# USB_Type_A_Female_Breakout.net
KiCad netlist of a schematic drawn in EAGLE
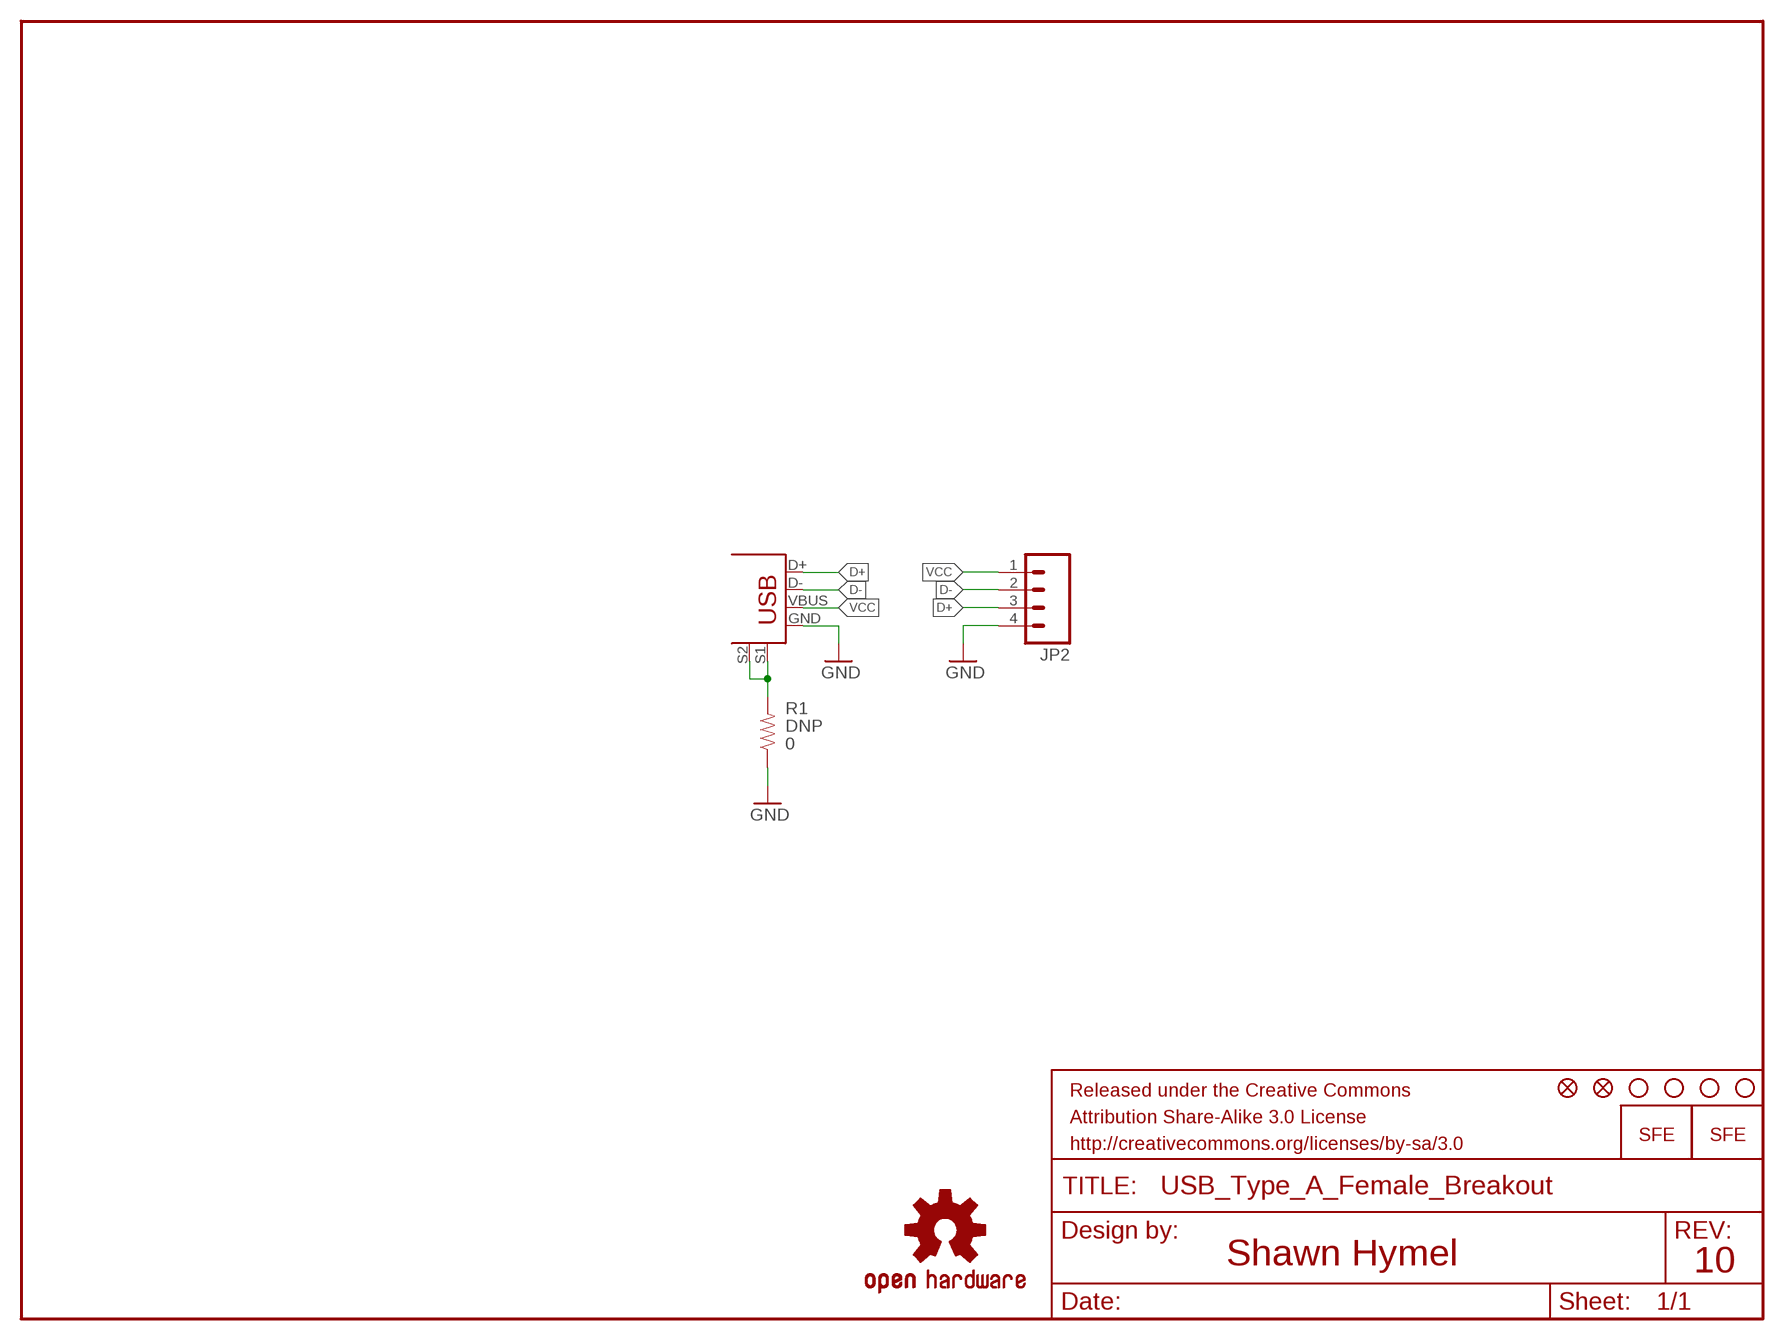
[diagram p0: schematic, sheet 1]

(export (version "E")
  (design (tool "Eeschema 10.0.6"))
  (components
    (comp (ref "FID1")
      (value "FIDUCIAL1X2")
      (footprint "eagle-import:FIDUCIAL-1X2")
      (libsource (lib "eagle-import") (part "FIDUCIAL1X2"))
    )
    (comp (ref "FID2")
      (value "FIDUCIAL1X2")
      (footprint "eagle-import:FIDUCIAL-1X2")
      (libsource (lib "eagle-import") (part "FIDUCIAL1X2"))
    )
    (comp (ref "FRAME1")
      (value "FRAME-LETTER")
      (footprint "eagle-import:CREATIVE_COMMONS")
      (libsource (lib "eagle-import") (part "FRAME-LETTER"))
    )
    (comp (ref "JP1")
      (value "USB+SHIELDUSB-A-S-NOSILK-FEMALE")
      (footprint "eagle-import:USB-A-S-NOSILK-FEMALE")
      (libsource (lib "eagle-import") (part "USB+SHIELDUSB-A-S-NOSILK-FEMALE"))
    )
    (comp (ref "JP2")
      (value "M04PTH")
      (footprint "eagle-import:1X04")
      (libsource (lib "eagle-import") (part "M04PTH"))
    )
    (comp (ref "LOGO1")
      (value "LOGO-SFENEW")
      (footprint "eagle-import:SFE-NEW-WEBLOGO")
      (libsource (lib "eagle-import") (part "LOGO-SFENEW"))
    )
    (comp (ref "LOGO2")
      (value "OSHW-LOGOS")
      (footprint "eagle-import:OSHW-LOGO-S")
      (libsource (lib "eagle-import") (part "OSHW-LOGOS"))
    )
    (comp (ref "LOGO3")
      (value "LOGO-SFESK")
      (footprint "eagle-import:SFE-LOGO-FLAME")
      (libsource (lib "eagle-import") (part "LOGO-SFESK"))
    )
    (comp (ref "R1")
      (value "0")
      (footprint "eagle-import:0603-RES")
      (fields (field (name "PLACE") "DNP"))
      (libsource (lib "eagle-import") (part "RESISTOR0603"))
    )
    (comp (ref "STANDOFF1")
      (value "STAND-OFF")
      (footprint "eagle-import:STAND-OFF")
      (libsource (lib "eagle-import") (part "STAND-OFF"))
    )
    (comp (ref "STANDOFF2")
      (value "STAND-OFF")
      (footprint "eagle-import:STAND-OFF")
      (libsource (lib "eagle-import") (part "STAND-OFF"))
    )
    (comp (ref "STANDOFF3")
      (value "STAND-OFF")
      (footprint "eagle-import:STAND-OFF")
      (libsource (lib "eagle-import") (part "STAND-OFF"))
    )
    (comp (ref "STANDOFF4")
      (value "STAND-OFF")
      (footprint "eagle-import:STAND-OFF")
      (libsource (lib "eagle-import") (part "STAND-OFF"))
    )
  )
  (nets
    (net (code "1") (name "D+") (class "Default")
      (node (ref "JP1") (pin "D+") (pinfunction "D+_D+") (pintype "bidirectional"))
      (node (ref "JP2") (pin "3") (pinfunction "3_3") (pintype "passive"))
    )
    (net (code "2") (name "D-") (class "Default")
      (node (ref "JP1") (pin "D-") (pinfunction "D-_D-") (pintype "bidirectional"))
      (node (ref "JP2") (pin "2") (pinfunction "2_2") (pintype "passive"))
    )
    (net (code "3") (name "GND") (class "Default")
      (node (ref "JP1") (pin "GND") (pinfunction "GND_GND") (pintype "bidirectional"))
      (node (ref "JP2") (pin "4") (pinfunction "4_4") (pintype "passive"))
      (node (ref "R1") (pin "1") (pinfunction "1_1") (pintype "passive"))
    )
    (net (code "4") (name "Net-(JP1-PadS1)") (class "Default")
      (node (ref "JP1") (pin "S1") (pinfunction "S1_S1") (pintype "bidirectional"))
      (node (ref "JP1") (pin "S2") (pinfunction "S2_S2") (pintype "bidirectional"))
      (node (ref "R1") (pin "2") (pinfunction "2_2") (pintype "passive"))
    )
    (net (code "5") (name "VCC") (class "Default")
      (node (ref "JP1") (pin "VBUS") (pinfunction "VBUS_VBUS") (pintype "bidirectional"))
      (node (ref "JP2") (pin "1") (pinfunction "1_1") (pintype "passive"))
    )
  )
)
